# STLink_Schematic.net
KiCad netlist of a schematic drawn in Altium Designer
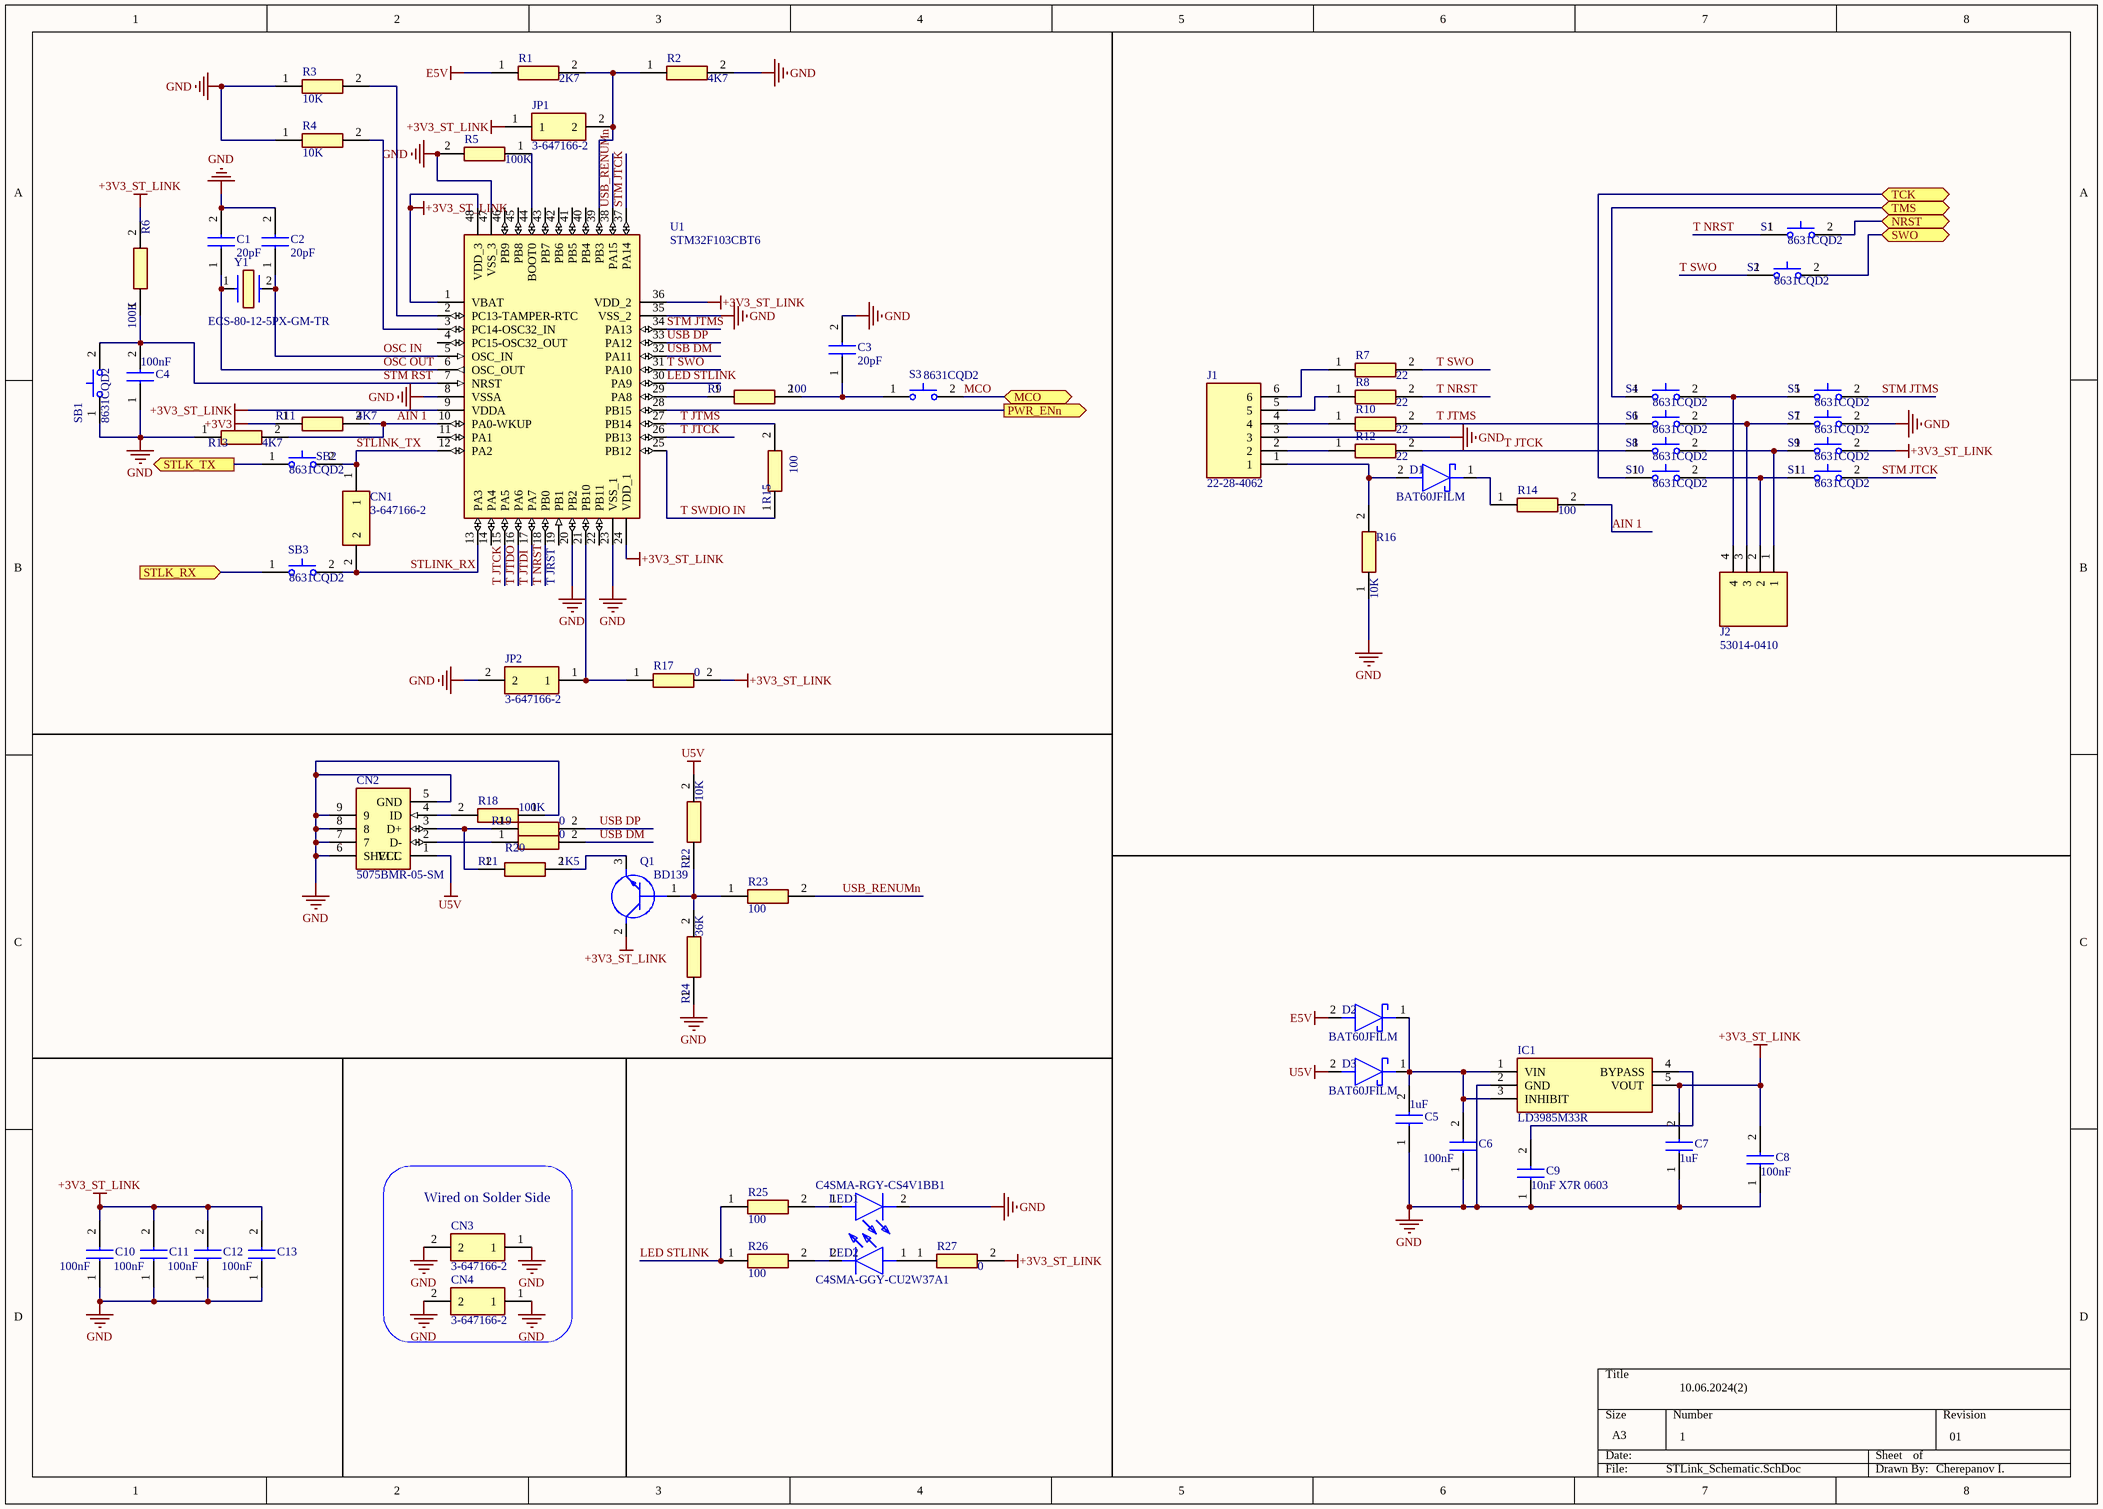
[diagram p0: STLink_Schematic.SchDoc]

(export (version "E")
  (design (tool "Eeschema 10.0.6"))
  (components
    (comp (ref "C1")
      (value "20pF")
      (footprint "SamacSys:C1206")
      (description "Capacitor")
      (fields (field (name "MANUFACTURER_PART_NUMBER") "C1206C200KCGACTU"))
      (libsource (lib "*") (part "C1206C200KCGACTU"))
    )
    (comp (ref "C2")
      (value "20pF")
      (footprint "SamacSys:C1206")
      (description "Capacitor")
      (fields (field (name "MANUFACTURER_PART_NUMBER") "C1206C200KCGACTU"))
      (libsource (lib "*") (part "C1206C200KCGACTU"))
    )
    (comp (ref "C3")
      (value "20pF")
      (footprint "SamacSys:C1206")
      (description "Capacitor")
      (fields (field (name "MANUFACTURER_PART_NUMBER") "C1206C200KCGACTU"))
      (libsource (lib "*") (part "C1206C200KCGACTU"))
    )
    (comp (ref "C4")
      (value "100nF")
      (footprint "SamacSys:CAPC1608X90N")
      (description "Capacitor")
      (fields
        (field (name "MANUFACTURER_PART_NUMBER") "KAM15AR71H104KM")
        (field (name "MOUSER PART NUMBER") "581-KAM15AR71H104KM")
      )
      (libsource (lib "*") (part "KAM15AR71H104KM"))
    )
    (comp (ref "C5")
      (value "1uF")
      (footprint "SamacSys:MAJx16")
      (description "Capacitor")
      (fields (field (name "MANUFACTURER_PART_NUMBER") "MAJCT168BB7105KTEA01"))
      (libsource (lib "*") (part "MAJCT168BB7105KTEA01"))
    )
    (comp (ref "C6")
      (value "100nF")
      (footprint "SamacSys:CAPC1608X90N")
      (description "Capacitor")
      (fields
        (field (name "MANUFACTURER_PART_NUMBER") "KAM15AR71H104KM")
        (field (name "MOUSER PART NUMBER") "581-KAM15AR71H104KM")
      )
      (libsource (lib "*") (part "KAM15AR71H104KM"))
    )
    (comp (ref "C7")
      (value "1uF")
      (footprint "SamacSys:MAJx16")
      (description "Capacitor")
      (fields (field (name "MANUFACTURER_PART_NUMBER") "MAJCT168BB7105KTEA01"))
      (libsource (lib "*") (part "MAJCT168BB7105KTEA01"))
    )
    (comp (ref "C8")
      (value "100nF")
      (footprint "SamacSys:CAPC1608X90N")
      (description "Capacitor")
      (fields
        (field (name "MANUFACTURER_PART_NUMBER") "KAM15AR71H104KM")
        (field (name "MOUSER PART NUMBER") "581-KAM15AR71H104KM")
      )
      (libsource (lib "*") (part "KAM15AR71H104KM"))
    )
    (comp (ref "C9")
      (value "10nF X7R 0603")
      (footprint "SamacSys:CAPC3316X145N")
      (description "Capacitor")
      (fields
        (field (name "MANUFACTURER_PART_NUMBER") "KGM31GCG2J103JU")
        (field (name "MOUSER PART NUMBER") "581-KGM31GCG2J103JU")
      )
      (libsource (lib "*") (part "KGM31GCG2J103JU"))
    )
    (comp (ref "C10")
      (value "100nF")
      (footprint "SamacSys:CAPC1608X90N")
      (description "Capacitor")
      (fields
        (field (name "MANUFACTURER_PART_NUMBER") "KAM15AR71H104KM")
        (field (name "MOUSER PART NUMBER") "581-KAM15AR71H104KM")
      )
      (libsource (lib "*") (part "KAM15AR71H104KM"))
    )
    (comp (ref "C11")
      (value "100nF")
      (footprint "SamacSys:CAPC1608X90N")
      (description "Capacitor")
      (fields
        (field (name "MANUFACTURER_PART_NUMBER") "KAM15AR71H104KM")
        (field (name "MOUSER PART NUMBER") "581-KAM15AR71H104KM")
      )
      (libsource (lib "*") (part "KAM15AR71H104KM"))
    )
    (comp (ref "C12")
      (value "100nF")
      (footprint "SamacSys:CAPC1608X90N")
      (description "Capacitor")
      (fields
        (field (name "MANUFACTURER_PART_NUMBER") "KAM15AR71H104KM")
        (field (name "MOUSER PART NUMBER") "581-KAM15AR71H104KM")
      )
      (libsource (lib "*") (part "KAM15AR71H104KM"))
    )
    (comp (ref "C13")
      (value "100nF")
      (footprint "SamacSys:CAPC1608X90N")
      (description "Capacitor")
      (fields
        (field (name "MANUFACTURER_PART_NUMBER") "KAM15AR71H104KM")
        (field (name "MOUSER PART NUMBER") "581-KAM15AR71H104KM")
      )
      (libsource (lib "*") (part "KAM15AR71H104KM"))
    )
    (comp (ref "CN1")
      (value "3-647166-2")
      (footprint "SamacSys:36471662")
      (description "Connector")
      (fields (field (name "MOUSER PART NUMBER") "571-3-647166-2"))
      (libsource (lib "") (part "3-647166-2_2"))
    )
    (comp (ref "CN2")
      (value "5075BMR-05-SM")
      (footprint "SamacSys:5075BMR05SM")
      (description "Connector")
      (libsource (lib "*") (part "5075BMR-05-SM"))
    )
    (comp (ref "CN3")
      (value "3-647166-2")
      (footprint "SamacSys:36471662")
      (description "Connector")
      (fields (field (name "MOUSER PART NUMBER") "571-3-647166-2"))
      (libsource (lib "*") (part "3-647166-2"))
    )
    (comp (ref "CN4")
      (value "3-647166-2")
      (footprint "SamacSys:36471662")
      (description "Connector")
      (fields (field (name "MOUSER PART NUMBER") "571-3-647166-2"))
      (libsource (lib "*") (part "3-647166-2"))
    )
    (comp (ref "D1")
      (value "BAT60JFILM")
      (footprint "SamacSys:SOD2513X117N")
      (description "Schottky Diode")
      (fields (field (name "MOUSER PART NUMBER") "511-BAT60JFILM"))
      (libsource (lib "*") (part "BAT60JFILM"))
    )
    (comp (ref "D2")
      (value "BAT60JFILM")
      (footprint "SamacSys:SOD2513X117N")
      (description "Schottky Diode")
      (fields (field (name "MOUSER PART NUMBER") "511-BAT60JFILM"))
      (libsource (lib "*") (part "BAT60JFILM"))
    )
    (comp (ref "D3")
      (value "BAT60JFILM")
      (footprint "SamacSys:SOD2513X117N")
      (description "Schottky Diode")
      (fields (field (name "MOUSER PART NUMBER") "511-BAT60JFILM"))
      (libsource (lib "*") (part "BAT60JFILM"))
    )
    (comp (ref "IC1")
      (value "LD3985M33R")
      (footprint "SamacSys:SOT95P280X145-5N")
      (description "Integrated Circuit")
      (fields (field (name "MOUSER PART NUMBER") "511-LD3985M33R"))
      (libsource (lib "*") (part "LD3985M33R"))
    )
    (comp (ref "J1")
      (value "22-28-4062")
      (footprint "SamacSys:HDRV6W66P0X254_1X6_1524X249X838P")
      (description "Connector")
      (fields (field (name "MOUSER PART NUMBER") "538-22-28-4062"))
      (libsource (lib "*") (part "22-28-4062"))
    )
    (comp (ref "J2")
      (value "53014-0410")
      (footprint "SamacSys:SHDR4W60P0X200_1X4_1200X435X1000P")
      (description "Connector")
      (fields (field (name "MOUSER PART NUMBER") "538-53014-0410"))
      (libsource (lib "*") (part "53014-0410"))
    )
    (comp (ref "JP1")
      (value "3-647166-2")
      (footprint "SamacSys:36471662")
      (description "Connector")
      (fields (field (name "MOUSER PART NUMBER") "571-3-647166-2"))
      (libsource (lib "") (part "3-647166-2_1"))
    )
    (comp (ref "JP2")
      (value "3-647166-2")
      (footprint "SamacSys:36471662")
      (description "Connector")
      (fields (field (name "MOUSER PART NUMBER") "571-3-647166-2"))
      (libsource (lib "*") (part "3-647166-2"))
    )
    (comp (ref "LED1")
      (value "C4SMA-RGY-CS4V1BB1")
      (footprint "SamacSys:C4SMARGYCS4V1BB1")
      (description "LED")
      (fields (field (name "MOUSER PART NUMBER") "941-C4SMARGYCS4V1BB1"))
      (libsource (lib "*") (part "C4SMA-RGY-CS4V1BB1"))
    )
    (comp (ref "LED2")
      (value "C4SMA-GGY-CU2W37A1")
      (footprint "SamacSys:C4SMAGGYCU2W37A1")
      (description "LED")
      (fields (field (name "MOUSER PART NUMBER") "941-C4SMAGGYCU2W37A1"))
      (libsource (lib "*") (part "C4SMA-GGY-CU2W37A1"))
    )
    (comp (ref "Q1")
      (value "BD139")
      (footprint "SamacSys:TO254P290X760X1320-3P")
      (description "Transistor BJT NPN")
      (fields (field (name "MOUSER PART NUMBER") "511-BD139"))
      (libsource (lib "*") (part "BD139"))
    )
    (comp (ref "R1")
      (value "2K7")
      (footprint "SamacSys:RESC3225X70N")
      (description "Resistor")
      (fields
        (field (name "MANUFACTURER_PART_NUMBER") "CRCW12102K70FKEAHP")
        (field (name "MOUSER PART NUMBER") "71-CRCW12102K70FKEAH")
      )
      (libsource (lib "*") (part "CRCW12102K70FKEAHP"))
    )
    (comp (ref "R2")
      (value "4K7")
      (footprint "SamacSys:RESC1005X37N")
      (description "Resistor")
      (fields
        (field (name "MANUFACTURER_PART_NUMBER") "MCS04020D4701BE000")
        (field (name "MOUSER PART NUMBER") "594-MCS04020D4701BE0")
      )
      (libsource (lib "*") (part "MCS04020D4701BE000"))
    )
    (comp (ref "R3")
      (value "10K")
      (footprint "SamacSys:RESC6331X80N")
      (description "Resistor")
      (fields
        (field (name "MANUFACTURER_PART_NUMBER") "CRM2512QJW-103ELF")
        (field (name "MOUSER PART NUMBER") "652-CRM2512QJW-103E")
      )
      (libsource (lib "*") (part "CRM2512QJW-103ELF"))
    )
    (comp (ref "R4")
      (value "10K")
      (footprint "SamacSys:RESC6331X80N")
      (description "Resistor")
      (fields
        (field (name "MANUFACTURER_PART_NUMBER") "CRM2512QJW-103ELF")
        (field (name "MOUSER PART NUMBER") "652-CRM2512QJW-103E")
      )
      (libsource (lib "*") (part "CRM2512QJW-103ELF"))
    )
    (comp (ref "R5")
      (value "100K")
      (footprint "SamacSys:RESC1005X40N")
      (description "Resistor")
      (fields
        (field (name "MANUFACTURER_PART_NUMBER") "SFR01MZPF1003")
        (field (name "MOUSER PART NUMBER") "755-SFR01MZPF1003")
      )
      (libsource (lib "") (part "SFR01MZPF1003_1"))
    )
    (comp (ref "R6")
      (value "100K")
      (footprint "SamacSys:RESC1005X40N")
      (description "Resistor")
      (fields
        (field (name "MANUFACTURER_PART_NUMBER") "SFR01MZPF1003")
        (field (name "MOUSER PART NUMBER") "755-SFR01MZPF1003")
      )
      (libsource (lib "*") (part "SFR01MZPF1003"))
    )
    (comp (ref "R7")
      (value "22")
      (footprint "SamacSys:ERA6AEB1020V")
      (description "Resistor")
      (fields
        (field (name "MANUFACTURER_PART_NUMBER") "ERA-6AHD220V")
        (field (name "MOUSER PART NUMBER") "667-ERA-6AHD220V")
      )
      (libsource (lib "*") (part "ERA-6AHD220V"))
    )
    (comp (ref "R8")
      (value "22")
      (footprint "SamacSys:ERA6AEB1020V")
      (description "Resistor")
      (fields
        (field (name "MANUFACTURER_PART_NUMBER") "ERA-6AHD220V")
        (field (name "MOUSER PART NUMBER") "667-ERA-6AHD220V")
      )
      (libsource (lib "*") (part "ERA-6AHD220V"))
    )
    (comp (ref "R9")
      (value "100")
      (footprint "SamacSys:RESC1005X37N")
      (description "Resistor")
      (fields
        (field (name "MANUFACTURER_PART_NUMBER") "MCS04020C1000FE000")
        (field (name "MOUSER PART NUMBER") "594-MCS04020C1000FE0")
      )
      (libsource (lib "*") (part "MCS04020C1000FE000"))
    )
    (comp (ref "R10")
      (value "22")
      (footprint "SamacSys:ERA6AEB1020V")
      (description "Resistor")
      (fields
        (field (name "MANUFACTURER_PART_NUMBER") "ERA-6AHD220V")
        (field (name "MOUSER PART NUMBER") "667-ERA-6AHD220V")
      )
      (libsource (lib "*") (part "ERA-6AHD220V"))
    )
    (comp (ref "R11")
      (value "4K7")
      (footprint "SamacSys:RESC1005X37N")
      (description "Resistor")
      (fields
        (field (name "MANUFACTURER_PART_NUMBER") "MCS04020D4701BE000")
        (field (name "MOUSER PART NUMBER") "594-MCS04020D4701BE0")
      )
      (libsource (lib "*") (part "MCS04020D4701BE000"))
    )
    (comp (ref "R12")
      (value "22")
      (footprint "SamacSys:ERA6AEB1020V")
      (description "Resistor")
      (fields
        (field (name "MANUFACTURER_PART_NUMBER") "ERA-6AHD220V")
        (field (name "MOUSER PART NUMBER") "667-ERA-6AHD220V")
      )
      (libsource (lib "*") (part "ERA-6AHD220V"))
    )
    (comp (ref "R13")
      (value "4K7")
      (footprint "SamacSys:RESC1005X37N")
      (description "Resistor")
      (fields
        (field (name "MANUFACTURER_PART_NUMBER") "MCS04020D4701BE000")
        (field (name "MOUSER PART NUMBER") "594-MCS04020D4701BE0")
      )
      (libsource (lib "*") (part "MCS04020D4701BE000"))
    )
    (comp (ref "R14")
      (value "100")
      (footprint "SamacSys:RESC1005X37N")
      (description "Resistor")
      (fields
        (field (name "MANUFACTURER_PART_NUMBER") "MCS04020C1000FE000")
        (field (name "MOUSER PART NUMBER") "594-MCS04020C1000FE0")
      )
      (libsource (lib "*") (part "MCS04020C1000FE000"))
    )
    (comp (ref "R15")
      (value "100")
      (footprint "SamacSys:RESC1005X37N")
      (description "Resistor")
      (fields
        (field (name "MANUFACTURER_PART_NUMBER") "MCS04020C1000FE000")
        (field (name "MOUSER PART NUMBER") "594-MCS04020C1000FE0")
      )
      (libsource (lib "") (part "MCS04020C1000FE000_1"))
    )
    (comp (ref "R16")
      (value "10K")
      (footprint "SamacSys:RESC1005X40N")
      (description "Resistor")
      (fields
        (field (name "MANUFACTURER_PART_NUMBER") "SFR01MZPF1003")
        (field (name "MOUSER PART NUMBER") "755-SFR01MZPF1003")
      )
      (libsource (lib "*") (part "SFR01MZPF1003"))
    )
    (comp (ref "R17")
      (value "0")
      (footprint "SamacSys:RESC2013X84N")
      (description "Resistor")
      (fields
        (field (name "MANUFACTURER_PART_NUMBER") "WSL080500000ZEA9")
        (field (name "MOUSER PART NUMBER") "71-WSL080500000ZEA9")
      )
      (libsource (lib "*") (part "WSL080500000ZEA9"))
    )
    (comp (ref "R18")
      (value "100K")
      (footprint "SamacSys:RESC1005X40N")
      (description "Resistor")
      (fields
        (field (name "MANUFACTURER_PART_NUMBER") "SFR01MZPF1003")
        (field (name "MOUSER PART NUMBER") "755-SFR01MZPF1003")
      )
      (libsource (lib "") (part "SFR01MZPF1003_1"))
    )
    (comp (ref "R19")
      (value "0")
      (footprint "SamacSys:RESC2013X84N")
      (description "Resistor")
      (fields
        (field (name "MANUFACTURER_PART_NUMBER") "WSL080500000ZEA9")
        (field (name "MOUSER PART NUMBER") "71-WSL080500000ZEA9")
      )
      (libsource (lib "*") (part "WSL080500000ZEA9"))
    )
    (comp (ref "R20")
      (value "0")
      (footprint "SamacSys:RESC2013X84N")
      (description "Resistor")
      (fields
        (field (name "MANUFACTURER_PART_NUMBER") "WSL080500000ZEA9")
        (field (name "MOUSER PART NUMBER") "71-WSL080500000ZEA9")
      )
      (libsource (lib "*") (part "WSL080500000ZEA9"))
    )
    (comp (ref "R21")
      (value "1K5")
      (footprint "SamacSys:RESC3116X65N")
      (description "Resistor")
      (fields
        (field (name "MANUFACTURER_PART_NUMBER") "CRCW12061K50FKEAHP")
        (field (name "MOUSER PART NUMBER") "71-CRCW12061K50FKEAH")
      )
      (libsource (lib "*") (part "CRCW12061K50FKEAHP"))
    )
    (comp (ref "R22")
      (value "10K")
      (footprint "SamacSys:RESC1005X40N")
      (description "Resistor")
      (fields
        (field (name "MANUFACTURER_PART_NUMBER") "SFR01MZPF1003")
        (field (name "MOUSER PART NUMBER") "755-SFR01MZPF1003")
      )
      (libsource (lib "*") (part "SFR01MZPF1003"))
    )
    (comp (ref "R23")
      (value "100")
      (footprint "SamacSys:RESC1005X37N")
      (description "Resistor")
      (fields
        (field (name "MANUFACTURER_PART_NUMBER") "MCS04020C1000FE000")
        (field (name "MOUSER PART NUMBER") "594-MCS04020C1000FE0")
      )
      (libsource (lib "*") (part "MCS04020C1000FE000"))
    )
    (comp (ref "R24")
      (value "36K")
      (footprint "SamacSys:RESC2012X55N")
      (description "Resistor")
      (fields (field (name "MANUFACTURER_PART_NUMBER") "TNPW080536K0BEEA"))
      (libsource (lib "*") (part "TNPW080536K0BEEA"))
    )
    (comp (ref "R25")
      (value "100")
      (footprint "SamacSys:RESC1005X37N")
      (description "Resistor")
      (fields
        (field (name "MANUFACTURER_PART_NUMBER") "MCS04020C1000FE000")
        (field (name "MOUSER PART NUMBER") "594-MCS04020C1000FE0")
      )
      (libsource (lib "*") (part "MCS04020C1000FE000"))
    )
    (comp (ref "R26")
      (value "100")
      (footprint "SamacSys:RESC1005X37N")
      (description "Resistor")
      (fields
        (field (name "MANUFACTURER_PART_NUMBER") "MCS04020C1000FE000")
        (field (name "MOUSER PART NUMBER") "594-MCS04020C1000FE0")
      )
      (libsource (lib "*") (part "MCS04020C1000FE000"))
    )
    (comp (ref "R27")
      (value "0")
      (footprint "SamacSys:RESC2013X84N")
      (description "Resistor")
      (fields
        (field (name "MANUFACTURER_PART_NUMBER") "WSL080500000ZEA9")
        (field (name "MOUSER PART NUMBER") "71-WSL080500000ZEA9")
      )
      (libsource (lib "*") (part "WSL080500000ZEA9"))
    )
    (comp (ref "S1")
      (value "8631CQD2")
      (footprint "SamacSys:8631CQD2")
      (description "Switch (2-Pin Push)")
      (fields (field (name "MOUSER PART NUMBER") "611-8631-261"))
      (libsource (lib "*") (part "8631CQD2"))
    )
    (comp (ref "S2")
      (value "8631CQD2")
      (footprint "SamacSys:8631CQD2")
      (description "Switch (2-Pin Push)")
      (fields (field (name "MOUSER PART NUMBER") "611-8631-261"))
      (libsource (lib "*") (part "8631CQD2"))
    )
    (comp (ref "S3")
      (value "8631CQD2")
      (footprint "SamacSys:8631CQD2")
      (description "Switch (2-Pin Push)")
      (fields (field (name "MOUSER PART NUMBER") "611-8631-261"))
      (libsource (lib "*") (part "8631CQD2"))
    )
    (comp (ref "S4")
      (value "8631CQD2")
      (footprint "SamacSys:8631CQD2")
      (description "Switch (2-Pin Push)")
      (fields (field (name "MOUSER PART NUMBER") "611-8631-261"))
      (libsource (lib "*") (part "8631CQD2"))
    )
    (comp (ref "S5")
      (value "8631CQD2")
      (footprint "SamacSys:8631CQD2")
      (description "Switch (2-Pin Push)")
      (fields (field (name "MOUSER PART NUMBER") "611-8631-261"))
      (libsource (lib "*") (part "8631CQD2"))
    )
    (comp (ref "S6")
      (value "8631CQD2")
      (footprint "SamacSys:8631CQD2")
      (description "Switch (2-Pin Push)")
      (fields (field (name "MOUSER PART NUMBER") "611-8631-261"))
      (libsource (lib "*") (part "8631CQD2"))
    )
    (comp (ref "S7")
      (value "8631CQD2")
      (footprint "SamacSys:8631CQD2")
      (description "Switch (2-Pin Push)")
      (fields (field (name "MOUSER PART NUMBER") "611-8631-261"))
      (libsource (lib "*") (part "8631CQD2"))
    )
    (comp (ref "S8")
      (value "8631CQD2")
      (footprint "SamacSys:8631CQD2")
      (description "Switch (2-Pin Push)")
      (fields (field (name "MOUSER PART NUMBER") "611-8631-261"))
      (libsource (lib "*") (part "8631CQD2"))
    )
    (comp (ref "S9")
      (value "8631CQD2")
      (footprint "SamacSys:8631CQD2")
      (description "Switch (2-Pin Push)")
      (fields (field (name "MOUSER PART NUMBER") "611-8631-261"))
      (libsource (lib "*") (part "8631CQD2"))
    )
    (comp (ref "S10")
      (value "8631CQD2")
      (footprint "SamacSys:8631CQD2")
      (description "Switch (2-Pin Push)")
      (fields (field (name "MOUSER PART NUMBER") "611-8631-261"))
      (libsource (lib "*") (part "8631CQD2"))
    )
    (comp (ref "S11")
      (value "8631CQD2")
      (footprint "SamacSys:8631CQD2")
      (description "Switch (2-Pin Push)")
      (fields (field (name "MOUSER PART NUMBER") "611-8631-261"))
      (libsource (lib "*") (part "8631CQD2"))
    )
    (comp (ref "SB1")
      (value "8631CQD2")
      (footprint "SamacSys:8631CQD2")
      (description "Switch (2-Pin Push)")
      (fields (field (name "MOUSER PART NUMBER") "611-8631-261"))
      (libsource (lib "*") (part "8631CQD2"))
    )
    (comp (ref "SB2")
      (value "8631CQD2")
      (footprint "SamacSys:8631CQD2")
      (description "Switch (2-Pin Push)")
      (fields (field (name "MOUSER PART NUMBER") "611-8631-261"))
      (libsource (lib "*") (part "8631CQD2"))
    )
    (comp (ref "SB3")
      (value "8631CQD2")
      (footprint "SamacSys:8631CQD2")
      (description "Switch (2-Pin Push)")
      (fields (field (name "MOUSER PART NUMBER") "611-8631-261"))
      (libsource (lib "*") (part "8631CQD2"))
    )
    (comp (ref "U1")
      (value "STM32F103CBT6")
      (footprint "SamacSys:QFP50P900X900X160-48N")
      (description "Integrated Circuit")
      (fields (field (name "MOUSER PART NUMBER") "511-STM32F103CBT6"))
      (libsource (lib "*") (part "STM32F103CBT6"))
    )
    (comp (ref "Y1")
      (value "ECS-80-12-5PX-GM-TR")
      (footprint "SamacSys:ECS80125PXGMTR")
      (description "Crystal or Oscillator")
      (fields (field (name "MOUSER PART NUMBER") "520-80-12-5PX-GM-TR"))
      (libsource (lib "*") (part "ECS-80-12-5PX-GM-TR"))
    )
  )
  (nets
    (net (code "1") (name "+3V3") (class "Default")
      (node (ref "R11") (pin "1") (pinfunction "1_1") (pintype "passive"))
    )
    (net (code "2") (name "+3V3_ST_LINK") (class "Default")
      (node (ref "C10") (pin "2") (pinfunction "2_2") (pintype "passive"))
      (node (ref "C11") (pin "2") (pinfunction "2_2") (pintype "passive"))
      (node (ref "C12") (pin "2") (pinfunction "2_2") (pintype "passive"))
      (node (ref "C13") (pin "2") (pinfunction "2_2") (pintype "passive"))
      (node (ref "C7") (pin "2") (pinfunction "2_2") (pintype "passive"))
      (node (ref "C8") (pin "2") (pinfunction "2_2") (pintype "passive"))
      (node (ref "IC1") (pin "5") (pinfunction "VOUT_5") (pintype "passive"))
      (node (ref "JP1") (pin "1") (pinfunction "1_1") (pintype "passive"))
      (node (ref "Q1") (pin "2") (pinfunction "C_2") (pintype "passive"))
      (node (ref "R17") (pin "2") (pinfunction "2_2") (pintype "passive"))
      (node (ref "R27") (pin "2") (pinfunction "2_2") (pintype "passive"))
      (node (ref "R6") (pin "2") (pinfunction "2_2") (pintype "passive"))
      (node (ref "S9") (pin "2") (pinfunction "N.O._2_2") (pintype "passive"))
      (node (ref "U1") (pin "1") (pinfunction "VBAT_1") (pintype "passive"))
      (node (ref "U1") (pin "24") (pinfunction "VDD_1_24") (pintype "passive"))
      (node (ref "U1") (pin "36") (pinfunction "VDD_2_36") (pintype "passive"))
      (node (ref "U1") (pin "48") (pinfunction "VDD_3_48") (pintype "passive"))
      (node (ref "U1") (pin "9") (pinfunction "VDDA_9") (pintype "passive"))
    )
    (net (code "3") (name "/AIN 1") (class "Default")
      (node (ref "R11") (pin "2") (pinfunction "2_2") (pintype "passive"))
      (node (ref "R13") (pin "2") (pinfunction "2_2") (pintype "passive"))
      (node (ref "R14") (pin "2") (pinfunction "2_2") (pintype "passive"))
      (node (ref "U1") (pin "10") (pinfunction "PA0-WKUP_10") (pintype "bidirectional"))
    )
    (net (code "4") (name "/LED STLINK") (class "Default")
      (node (ref "R25") (pin "1") (pinfunction "1_1") (pintype "passive"))
      (node (ref "R26") (pin "1") (pinfunction "1_1") (pintype "passive"))
      (node (ref "U1") (pin "30") (pinfunction "PA9_30") (pintype "bidirectional"))
    )
    (net (code "5") (name "/MCO") (class "Default")
      (node (ref "S3") (pin "2") (pinfunction "N.O._2_2") (pintype "passive"))
    )
    (net (code "6") (name "/NRST") (class "Default")
      (node (ref "S1") (pin "2") (pinfunction "N.O._2_2") (pintype "passive"))
    )
    (net (code "7") (name "/OSC IN") (class "Default")
      (node (ref "C2") (pin "1") (pinfunction "1_1") (pintype "passive"))
      (node (ref "U1") (pin "5") (pinfunction "OSC_IN_5") (pintype "input"))
      (node (ref "Y1") (pin "2") (pinfunction "2_2") (pintype "passive"))
    )
    (net (code "8") (name "/OSC OUT") (class "Default")
      (node (ref "C1") (pin "1") (pinfunction "1_1") (pintype "passive"))
      (node (ref "U1") (pin "6") (pinfunction "OSC_OUT_6") (pintype "output"))
      (node (ref "Y1") (pin "1") (pinfunction "1_1") (pintype "passive"))
    )
    (net (code "9") (name "/PWR_ENn") (class "Default")
      (node (ref "U1") (pin "28") (pinfunction "PB15_28") (pintype "bidirectional"))
    )
    (net (code "10") (name "/STLINK_RX") (class "Default")
      (node (ref "CN1") (pin "2") (pinfunction "2_2") (pintype "passive"))
      (node (ref "SB3") (pin "2") (pinfunction "N.O._2_2") (pintype "passive"))
      (node (ref "U1") (pin "13") (pinfunction "PA3_13") (pintype "bidirectional"))
    )
    (net (code "11") (name "/STLINK_TX") (class "Default")
      (node (ref "CN1") (pin "1") (pinfunction "1_1") (pintype "passive"))
      (node (ref "SB2") (pin "2") (pinfunction "N.O._2_2") (pintype "passive"))
      (node (ref "U1") (pin "12") (pinfunction "PA2_12") (pintype "bidirectional"))
    )
    (net (code "12") (name "/STLK_RX") (class "Default")
      (node (ref "SB3") (pin "1") (pinfunction "N.O._1_1") (pintype "passive"))
    )
    (net (code "13") (name "/STLK_TX") (class "Default")
      (node (ref "SB2") (pin "1") (pinfunction "N.O._1_1") (pintype "passive"))
    )
    (net (code "14") (name "/STM JTCK") (class "Default")
      (node (ref "S11") (pin "2") (pinfunction "N.O._2_2") (pintype "passive"))
      (node (ref "U1") (pin "37") (pinfunction "PA14_37") (pintype "bidirectional"))
    )
    (net (code "15") (name "/STM JTMS") (class "Default")
      (node (ref "S5") (pin "2") (pinfunction "N.O._2_2") (pintype "passive"))
      (node (ref "U1") (pin "34") (pinfunction "PA13_34") (pintype "bidirectional"))
    )
    (net (code "16") (name "/STM RST") (class "Default")
      (node (ref "C4") (pin "2") (pinfunction "2_2") (pintype "passive"))
      (node (ref "R6") (pin "1") (pinfunction "1_1") (pintype "passive"))
      (node (ref "SB1") (pin "2") (pinfunction "N.O._2_2") (pintype "passive"))
      (node (ref "U1") (pin "7") (pinfunction "NRST_7") (pintype "input"))
    )
    (net (code "17") (name "/SWO") (class "Default")
      (node (ref "S2") (pin "2") (pinfunction "N.O._2_2") (pintype "passive"))
    )
    (net (code "18") (name "/T JTCK") (class "Default")
      (node (ref "R12") (pin "2") (pinfunction "2_2") (pintype "passive"))
      (node (ref "S8") (pin "1") (pinfunction "N.O._1_1") (pintype "passive"))
      (node (ref "U1") (pin "15") (pinfunction "PA5_15") (pintype "bidirectional"))
      (node (ref "U1") (pin "26") (pinfunction "PB13_26") (pintype "bidirectional"))
    )
    (net (code "19") (name "/T JTDI") (class "Default")
      (node (ref "U1") (pin "17") (pinfunction "PA7_17") (pintype "bidirectional"))
    )
    (net (code "20") (name "/T JTDO") (class "Default")
      (node (ref "U1") (pin "16") (pinfunction "PA6_16") (pintype "bidirectional"))
    )
    (net (code "21") (name "/T JTMS") (class "Default")
      (node (ref "R10") (pin "2") (pinfunction "2_2") (pintype "passive"))
      (node (ref "R15") (pin "2") (pinfunction "2_2") (pintype "passive"))
      (node (ref "S6") (pin "1") (pinfunction "N.O._1_1") (pintype "passive"))
      (node (ref "U1") (pin "27") (pinfunction "PB14_27") (pintype "bidirectional"))
    )
    (net (code "22") (name "/T NRST") (class "Default")
      (node (ref "R8") (pin "2") (pinfunction "2_2") (pintype "passive"))
      (node (ref "S1") (pin "1") (pinfunction "N.O._1_1") (pintype "passive"))
      (node (ref "U1") (pin "18") (pinfunction "PB0_18") (pintype "bidirectional"))
    )
    (net (code "23") (name "/T SWDIO IN") (class "Default")
      (node (ref "R15") (pin "1") (pinfunction "1_1") (pintype "passive"))
      (node (ref "U1") (pin "25") (pinfunction "PB12_25") (pintype "bidirectional"))
    )
    (net (code "24") (name "/T SWO") (class "Default")
      (node (ref "R7") (pin "2") (pinfunction "2_2") (pintype "passive"))
      (node (ref "S2") (pin "1") (pinfunction "N.O._1_1") (pintype "passive"))
      (node (ref "U1") (pin "31") (pinfunction "PA10_31") (pintype "bidirectional"))
    )
    (net (code "25") (name "/TCK") (class "Default")
      (node (ref "S10") (pin "1") (pinfunction "N.O._1_1") (pintype "passive"))
    )
    (net (code "26") (name "/TMS") (class "Default")
      (node (ref "S4") (pin "1") (pinfunction "N.O._1_1") (pintype "passive"))
    )
    (net (code "27") (name "/USB DM") (class "Default")
      (node (ref "R20") (pin "2") (pinfunction "2_2") (pintype "passive"))
      (node (ref "U1") (pin "32") (pinfunction "PA11_32") (pintype "bidirectional"))
    )
    (net (code "28") (name "/USB DP") (class "Default")
      (node (ref "R19") (pin "2") (pinfunction "2_2") (pintype "passive"))
      (node (ref "U1") (pin "33") (pinfunction "PA12_33") (pintype "bidirectional"))
    )
    (net (code "29") (name "/USB_RENUMn") (class "Default")
      (node (ref "R23") (pin "2") (pinfunction "2_2") (pintype "passive"))
      (node (ref "U1") (pin "38") (pinfunction "PA15_38") (pintype "bidirectional"))
    )
    (net (code "30") (name "E5V") (class "Default")
      (node (ref "D2") (pin "2") (pinfunction "A_2") (pintype "passive"))
      (node (ref "R1") (pin "1") (pinfunction "1_1") (pintype "passive"))
    )
    (net (code "31") (name "GND") (class "Default")
      (node (ref "C1") (pin "2") (pinfunction "2_2") (pintype "passive"))
      (node (ref "C10") (pin "1") (pinfunction "1_1") (pintype "passive"))
      (node (ref "C11") (pin "1") (pinfunction "1_1") (pintype "passive"))
      (node (ref "C12") (pin "1") (pinfunction "1_1") (pintype "passive"))
      (node (ref "C13") (pin "1") (pinfunction "1_1") (pintype "passive"))
      (node (ref "C2") (pin "2") (pinfunction "2_2") (pintype "passive"))
      (node (ref "C3") (pin "2") (pinfunction "2_2") (pintype "passive"))
      (node (ref "C4") (pin "1") (pinfunction "1_1") (pintype "passive"))
      (node (ref "C5") (pin "1") (pinfunction "1_1") (pintype "passive"))
      (node (ref "C6") (pin "1") (pinfunction "1_1") (pintype "passive"))
      (node (ref "C7") (pin "1") (pinfunction "1_1") (pintype "passive"))
      (node (ref "C8") (pin "1") (pinfunction "1_1") (pintype "passive"))
      (node (ref "C9") (pin "1") (pinfunction "1_1") (pintype "passive"))
      (node (ref "CN2") (pin "5") (pinfunction "GND_5") (pintype "passive"))
      (node (ref "CN2") (pin "6") (pinfunction "SHELL_6") (pintype "passive"))
      (node (ref "CN2") (pin "7") (pinfunction "7_7") (pintype "passive"))
      (node (ref "CN2") (pin "8") (pinfunction "8_8") (pintype "passive"))
      (node (ref "CN2") (pin "9") (pinfunction "9_9") (pintype "passive"))
      (node (ref "CN3") (pin "1") (pinfunction "1_1") (pintype "passive"))
      (node (ref "CN3") (pin "2") (pinfunction "2_2") (pintype "passive"))
      (node (ref "CN4") (pin "1") (pinfunction "1_1") (pintype "passive"))
      (node (ref "CN4") (pin "2") (pinfunction "2_2") (pintype "passive"))
      (node (ref "IC1") (pin "2") (pinfunction "GND_2") (pintype "passive"))
      (node (ref "J1") (pin "3") (pinfunction "3_3") (pintype "passive"))
      (node (ref "JP2") (pin "2") (pinfunction "2_2") (pintype "passive"))
      (node (ref "LED1") (pin "2") (pinfunction "K_2") (pintype "passive"))
      (node (ref "R13") (pin "1") (pinfunction "1_1") (pintype "passive"))
      (node (ref "R16") (pin "1") (pinfunction "1_1") (pintype "passive"))
      (node (ref "R18") (pin "1") (pinfunction "1_1") (pintype "passive"))
      (node (ref "R2") (pin "2") (pinfunction "2_2") (pintype "passive"))
      (node (ref "R24") (pin "1") (pinfunction "1_1") (pintype "passive"))
      (node (ref "R3") (pin "1") (pinfunction "1_1") (pintype "passive"))
      (node (ref "R4") (pin "1") (pinfunction "1_1") (pintype "passive"))
      (node (ref "R5") (pin "2") (pinfunction "2_2") (pintype "passive"))
      (node (ref "S7") (pin "2") (pinfunction "N.O._2_2") (pintype "passive"))
      (node (ref "SB1") (pin "1") (pinfunction "N.O._1_1") (pintype "passive"))
      (node (ref "U1") (pin "20") (pinfunction "PB2_20") (pintype "bidirectional"))
      (node (ref "U1") (pin "23") (pinfunction "VSS_1_23") (pintype "passive"))
      (node (ref "U1") (pin "35") (pinfunction "VSS_2_35") (pintype "passive"))
      (node (ref "U1") (pin "47") (pinfunction "VSS_3_47") (pintype "passive"))
      (node (ref "U1") (pin "8") (pinfunction "VSSA_8") (pintype "passive"))
    )
    (net (code "32") (name "Net-(CN2-D+)") (class "Default")
      (node (ref "CN2") (pin "3") (pinfunction "D+_3") (pintype "bidirectional"))
      (node (ref "R19") (pin "1") (pinfunction "1_1") (pintype "passive"))
      (node (ref "R21") (pin "1") (pinfunction "1_1") (pintype "passive"))
    )
    (net (code "33") (name "Net-(CN2-D-)") (class "Default")
      (node (ref "CN2") (pin "2") (pinfunction "D-_2") (pintype "bidirectional"))
      (node (ref "R20") (pin "1") (pinfunction "1_1") (pintype "passive"))
    )
    (net (code "34") (name "Net-(CN2-ID)") (class "Default")
      (node (ref "CN2") (pin "4") (pinfunction "ID_4") (pintype "input"))
      (node (ref "R18") (pin "2") (pinfunction "2_2") (pintype "passive"))
    )
    (net (code "35") (name "Net-(D1-A)") (class "Default")
      (node (ref "D1") (pin "2") (pinfunction "A_2") (pintype "passive"))
      (node (ref "J1") (pin "1") (pinfunction "1_1") (pintype "passive"))
      (node (ref "R16") (pin "2") (pinfunction "2_2") (pintype "passive"))
    )
    (net (code "36") (name "Net-(D1-K)") (class "Default")
      (node (ref "D1") (pin "1") (pinfunction "K_1") (pintype "passive"))
      (node (ref "R14") (pin "1") (pinfunction "1_1") (pintype "passive"))
    )
    (net (code "37") (name "Net-(D2-K)") (class "Default")
      (node (ref "C5") (pin "2") (pinfunction "2_2") (pintype "passive"))
      (node (ref "C6") (pin "2") (pinfunction "2_2") (pintype "passive"))
      (node (ref "D2") (pin "1") (pinfunction "K_1") (pintype "passive"))
      (node (ref "D3") (pin "1") (pinfunction "K_1") (pintype "passive"))
      (node (ref "IC1") (pin "1") (pinfunction "VIN_1") (pintype "passive"))
      (node (ref "IC1") (pin "3") (pinfunction "INHIBIT_3") (pintype "passive"))
    )
    (net (code "38") (name "Net-(IC1-BYPASS)") (class "Default")
      (node (ref "C9") (pin "2") (pinfunction "2_2") (pintype "passive"))
      (node (ref "IC1") (pin "4") (pinfunction "BYPASS_4") (pintype "passive"))
    )
    (net (code "39") (name "Net-(J1-Pad2)") (class "Default")
      (node (ref "J1") (pin "2") (pinfunction "2_2") (pintype "passive"))
      (node (ref "R12") (pin "1") (pinfunction "1_1") (pintype "passive"))
    )
    (net (code "40") (name "Net-(J1-Pad4)") (class "Default")
      (node (ref "J1") (pin "4") (pinfunction "4_4") (pintype "passive"))
      (node (ref "R10") (pin "1") (pinfunction "1_1") (pintype "passive"))
    )
    (net (code "41") (name "Net-(J1-Pad5)") (class "Default")
      (node (ref "J1") (pin "5") (pinfunction "5_5") (pintype "passive"))
      (node (ref "R8") (pin "1") (pinfunction "1_1") (pintype "passive"))
    )
    (net (code "42") (name "Net-(J1-Pad6)") (class "Default")
      (node (ref "J1") (pin "6") (pinfunction "6_6") (pintype "passive"))
      (node (ref "R7") (pin "1") (pinfunction "1_1") (pintype "passive"))
    )
    (net (code "43") (name "Net-(LED1-A)") (class "Default")
      (node (ref "LED1") (pin "1") (pinfunction "A_1") (pintype "passive"))
      (node (ref "R25") (pin "2") (pinfunction "2_2") (pintype "passive"))
    )
    (net (code "44") (name "Net-(LED2-A)") (class "Default")
      (node (ref "LED2") (pin "1") (pinfunction "A_1") (pintype "passive"))
      (node (ref "R27") (pin "1") (pinfunction "1_1") (pintype "passive"))
    )
    (net (code "45") (name "Net-(LED2-K)") (class "Default")
      (node (ref "LED2") (pin "2") (pinfunction "K_2") (pintype "passive"))
      (node (ref "R26") (pin "2") (pinfunction "2_2") (pintype "passive"))
    )
    (net (code "46") (name "Net-(Q1-B)") (class "Default")
      (node (ref "Q1") (pin "1") (pinfunction "B_1") (pintype "passive"))
      (node (ref "R22") (pin "1") (pinfunction "1_1") (pintype "passive"))
      (node (ref "R23") (pin "1") (pinfunction "1_1") (pintype "passive"))
      (node (ref "R24") (pin "2") (pinfunction "2_2") (pintype "passive"))
    )
    (net (code "47") (name "Net-(Q1-E)") (class "Default")
      (node (ref "Q1") (pin "3") (pinfunction "E_3") (pintype "passive"))
      (node (ref "R21") (pin "2") (pinfunction "2_2") (pintype "passive"))
    )
    (net (code "48") (name "Net-(S3-N.O._1)") (class "Default")
      (node (ref "C3") (pin "1") (pinfunction "1_1") (pintype "passive"))
      (node (ref "R9") (pin "2") (pinfunction "2_2") (pintype "passive"))
      (node (ref "S3") (pin "1") (pinfunction "N.O._1_1") (pintype "passive"))
    )
    (net (code "49") (name "Net-(S4-N.O._2)") (class "Default")
      (node (ref "J2") (pin "4") (pinfunction "4_4") (pintype "passive"))
      (node (ref "S4") (pin "2") (pinfunction "N.O._2_2") (pintype "passive"))
      (node (ref "S5") (pin "1") (pinfunction "N.O._1_1") (pintype "passive"))
    )
    (net (code "50") (name "Net-(S6-N.O._2)") (class "Default")
      (node (ref "J2") (pin "3") (pinfunction "3_3") (pintype "passive"))
      (node (ref "S6") (pin "2") (pinfunction "N.O._2_2") (pintype "passive"))
      (node (ref "S7") (pin "1") (pinfunction "N.O._1_1") (pintype "passive"))
    )
    (net (code "51") (name "Net-(S8-N.O._2)") (class "Default")
      (node (ref "J2") (pin "1") (pinfunction "1_1") (pintype "passive"))
      (node (ref "S8") (pin "2") (pinfunction "N.O._2_2") (pintype "passive"))
      (node (ref "S9") (pin "1") (pinfunction "N.O._1_1") (pintype "passive"))
    )
    (net (code "52") (name "Net-(S10-N.O._2)") (class "Default")
      (node (ref "J2") (pin "2") (pinfunction "2_2") (pintype "passive"))
      (node (ref "S10") (pin "2") (pinfunction "N.O._2_2") (pintype "passive"))
      (node (ref "S11") (pin "1") (pinfunction "N.O._1_1") (pintype "passive"))
    )
    (net (code "53") (name "Net-(U1-BOOT0)") (class "Default")
      (node (ref "R5") (pin "1") (pinfunction "1_1") (pintype "passive"))
      (node (ref "U1") (pin "44") (pinfunction "BOOT0_44") (pintype "bidirectional"))
    )
    (net (code "54") (name "Net-(U1-PA8)") (class "Default")
      (node (ref "R9") (pin "1") (pinfunction "1_1") (pintype "passive"))
      (node (ref "U1") (pin "29") (pinfunction "PA8_29") (pintype "bidirectional"))
    )
    (net (code "55") (name "Net-(U1-PB3)") (class "Default")
      (node (ref "JP1") (pin "2") (pinfunction "2_2") (pintype "passive"))
      (node (ref "R1") (pin "2") (pinfunction "2_2") (pintype "passive"))
      (node (ref "R2") (pin "1") (pinfunction "1_1") (pintype "passive"))
      (node (ref "U1") (pin "39") (pinfunction "PB3_39") (pintype "bidirectional"))
    )
    (net (code "56") (name "Net-(U1-PB10)") (class "Default")
      (node (ref "JP2") (pin "1") (pinfunction "1_1") (pintype "passive"))
      (node (ref "R17") (pin "1") (pinfunction "1_1") (pintype "passive"))
      (node (ref "U1") (pin "21") (pinfunction "PB10_21") (pintype "bidirectional"))
    )
    (net (code "57") (name "Net-(U1-PC13-TAMPER-RTC)") (class "Default")
      (node (ref "R3") (pin "2") (pinfunction "2_2") (pintype "passive"))
      (node (ref "U1") (pin "2") (pinfunction "PC13-TAMPER-RTC_2") (pintype "bidirectional"))
    )
    (net (code "58") (name "Net-(U1-PC14-OSC32_IN)") (class "Default")
      (node (ref "R4") (pin "2") (pinfunction "2_2") (pintype "passive"))
      (node (ref "U1") (pin "3") (pinfunction "PC14-OSC32_IN_3") (pintype "bidirectional"))
    )
    (net (code "59") (name "U5V") (class "Default")
      (node (ref "CN2") (pin "1") (pinfunction "VCC_1") (pintype "passive"))
      (node (ref "D3") (pin "2") (pinfunction "A_2") (pintype "passive"))
      (node (ref "R22") (pin "2") (pinfunction "2_2") (pintype "passive"))
    )
    (net (code "60") (name "unconnected-(U1-PA1-Pad11)") (class "Default")
      (node (ref "U1") (pin "11") (pinfunction "PA1_11") (pintype "bidirectional"))
    )
    (net (code "61") (name "unconnected-(U1-PA4-Pad14)") (class "Default")
      (node (ref "U1") (pin "14") (pinfunction "PA4_14") (pintype "bidirectional"))
    )
    (net (code "62") (name "unconnected-(U1-PB1-Pad19)") (class "Default")
      (node (ref "U1") (pin "19") (pinfunction "PB1_19") (pintype "input"))
    )
    (net (code "63") (name "unconnected-(U1-PB4-Pad40)") (class "Default")
      (node (ref "U1") (pin "40") (pinfunction "PB4_40") (pintype "bidirectional"))
    )
    (net (code "64") (name "unconnected-(U1-PB5-Pad41)") (class "Default")
      (node (ref "U1") (pin "41") (pinfunction "PB5_41") (pintype "bidirectional"))
    )
    (net (code "65") (name "unconnected-(U1-PB6-Pad42)") (class "Default")
      (node (ref "U1") (pin "42") (pinfunction "PB6_42") (pintype "bidirectional"))
    )
    (net (code "66") (name "unconnected-(U1-PB7-Pad43)") (class "Default")
      (node (ref "U1") (pin "43") (pinfunction "PB7_43") (pintype "bidirectional"))
    )
    (net (code "67") (name "unconnected-(U1-PB8-Pad45)") (class "Default")
      (node (ref "U1") (pin "45") (pinfunction "PB8_45") (pintype "bidirectional"))
    )
    (net (code "68") (name "unconnected-(U1-PB9-Pad46)") (class "Default")
      (node (ref "U1") (pin "46") (pinfunction "PB9_46") (pintype "bidirectional"))
    )
    (net (code "69") (name "unconnected-(U1-PB11-Pad22)") (class "Default")
      (node (ref "U1") (pin "22") (pinfunction "PB11_22") (pintype "bidirectional"))
    )
    (net (code "70") (name "unconnected-(U1-PC15-OSC32_OUT-Pad4)") (class "Default")
      (node (ref "U1") (pin "4") (pinfunction "PC15-OSC32_OUT_4") (pintype "bidirectional"))
    )
  )
)
